# Feedback.net
KiCad netlist of a schematic drawn in Altium Designer
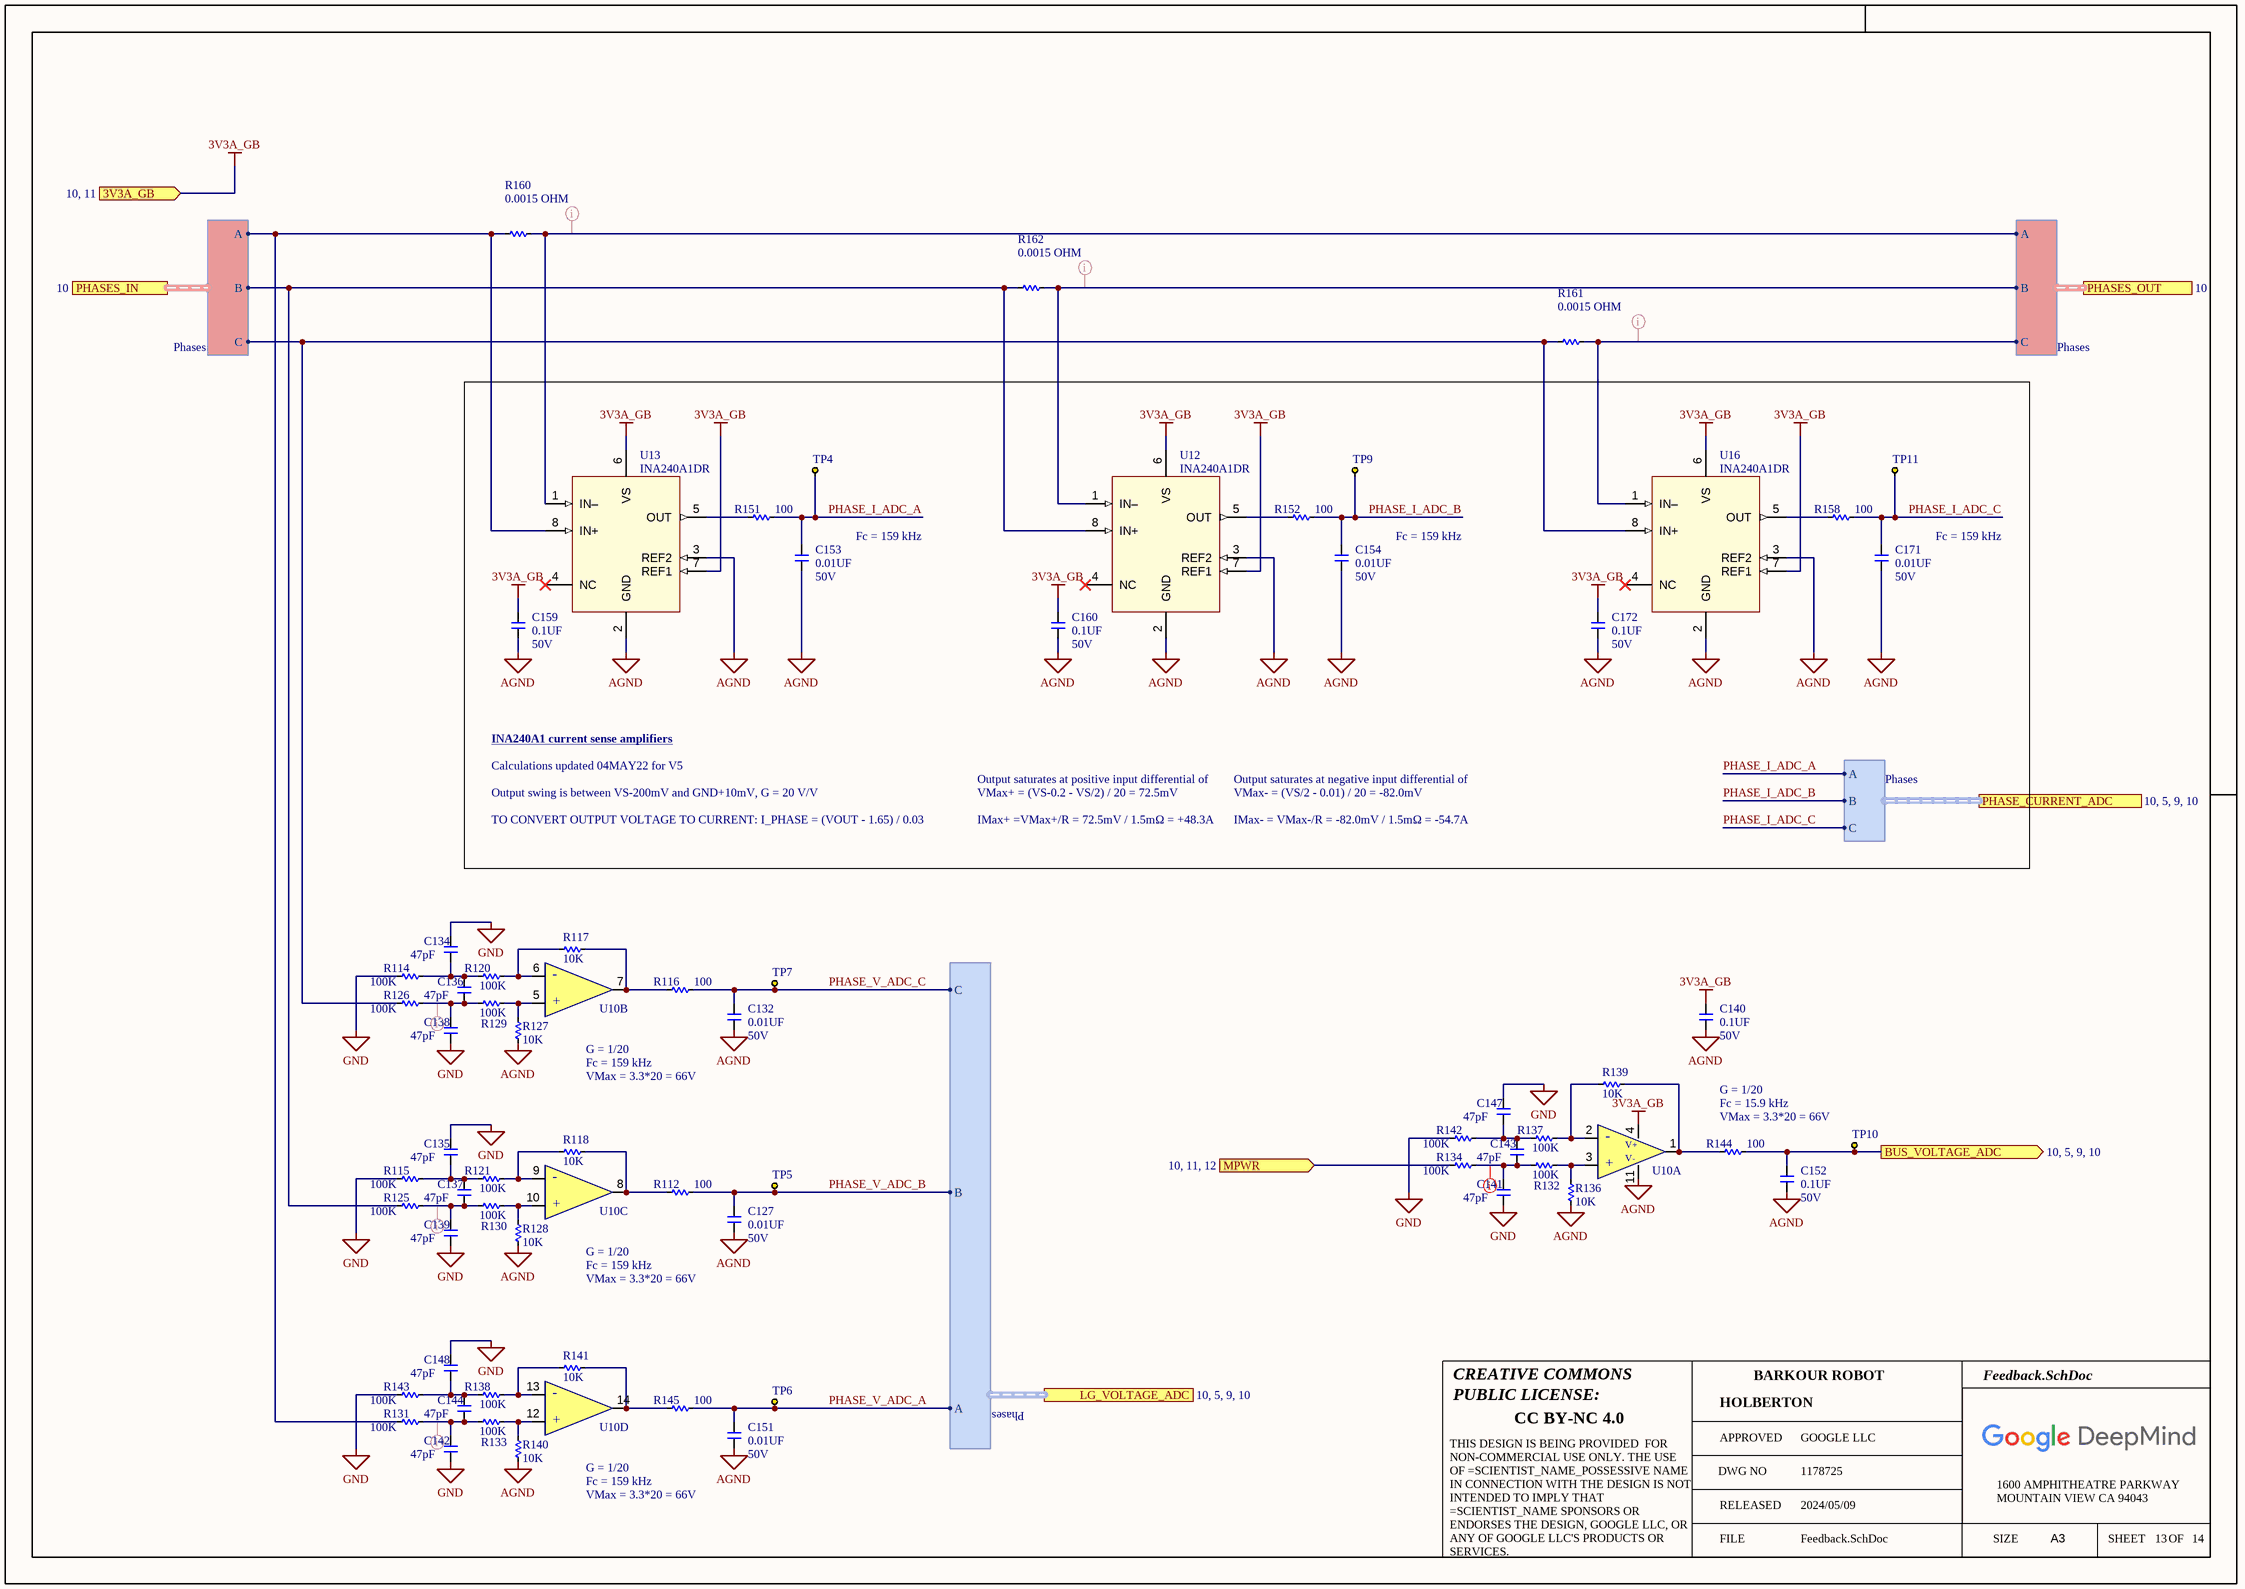
[diagram p0: Feedback.SchDoc]

(export (version "E")
  (design (tool "Eeschema 10.0.6"))
  (components
    (comp (ref "C127")
      (value "0.01UF")
      (footprint "C0402")
      (description "CAP, CER, X7R, 0.01uF, 50V, 20%, 0402, 0.56mm T")
      (fields
        (field (name "MFG") "KEMET")
        (field (name "VOLTAGE") "50V")
        (field (name "Comment") "__Template_Cap")
      )
      (libsource (lib "AltiumReleaseLibDB") (part "__Template_Cap"))
    )
    (comp (ref "C132")
      (value "0.01UF")
      (footprint "C0402")
      (description "CAP, CER, X7R, 0.01uF, 50V, 20%, 0402, 0.56mm T")
      (fields
        (field (name "MFG") "KEMET")
        (field (name "VOLTAGE") "50V")
        (field (name "Comment") "__Template_Cap")
      )
      (libsource (lib "AltiumReleaseLibDB") (part "__Template_Cap"))
    )
    (comp (ref "C134")
      (value "47pF")
      (footprint "C0402")
      (description "CAP, CER, C0G, 47PF, 5%, 50V, 0402")
      (fields (field (name "MFG") "TDK") (field (name "VOLTAGE") "50V"))
      (libsource (lib "AltiumReleaseLibDB") (part "__Template_Cap"))
    )
    (comp (ref "C135")
      (value "47pF")
      (footprint "C0402")
      (description "CAP, CER, C0G, 47PF, 5%, 50V, 0402")
      (fields (field (name "MFG") "TDK") (field (name "VOLTAGE") "50V"))
      (libsource (lib "AltiumReleaseLibDB") (part "__Template_Cap"))
    )
    (comp (ref "C136")
      (value "47pF")
      (footprint "C0402")
      (description "CAP, CER, C0G, 47PF, 5%, 50V, 0402")
      (fields (field (name "MFG") "TDK") (field (name "VOLTAGE") "50V"))
      (libsource (lib "AltiumReleaseLibDB") (part "__Template_Cap"))
    )
    (comp (ref "C137")
      (value "47pF")
      (footprint "C0402")
      (description "CAP, CER, C0G, 47PF, 5%, 50V, 0402")
      (fields (field (name "MFG") "TDK") (field (name "VOLTAGE") "50V"))
      (libsource (lib "AltiumReleaseLibDB") (part "__Template_Cap"))
    )
    (comp (ref "C138")
      (value "47pF")
      (footprint "C0402")
      (description "CAP, CER, C0G, 47PF, 5%, 50V, 0402")
      (fields (field (name "MFG") "TDK") (field (name "VOLTAGE") "50V"))
      (libsource (lib "AltiumReleaseLibDB") (part "__Template_Cap"))
    )
    (comp (ref "C139")
      (value "47pF")
      (footprint "C0402")
      (description "CAP, CER, C0G, 47PF, 5%, 50V, 0402")
      (fields (field (name "MFG") "TDK") (field (name "VOLTAGE") "50V"))
      (libsource (lib "AltiumReleaseLibDB") (part "__Template_Cap"))
    )
    (comp (ref "C140")
      (value "0.1UF")
      (footprint "C0402")
      (description "CAP, CER, X5R, 0.1uF, 10%, 50V, 0402, 0.55mm")
      (fields
        (field (name "MFG") "YAGEO")
        (field (name "VOLTAGE") "50V")
        (field (name "Comment") "__Template_Cap")
      )
      (libsource (lib "AltiumReleaseLibDB") (part "__Template_Cap"))
    )
    (comp (ref "C141")
      (value "47pF")
      (footprint "C0402")
      (description "CAP, CER, C0G, 47PF, 5%, 50V, 0402")
      (fields (field (name "MFG") "TDK") (field (name "VOLTAGE") "50V"))
      (libsource (lib "AltiumReleaseLibDB") (part "__Template_Cap"))
    )
    (comp (ref "C142")
      (value "47pF")
      (footprint "C0402")
      (description "CAP, CER, C0G, 47PF, 5%, 50V, 0402")
      (fields (field (name "MFG") "TDK") (field (name "VOLTAGE") "50V"))
      (libsource (lib "AltiumReleaseLibDB") (part "__Template_Cap"))
    )
    (comp (ref "C143")
      (value "47pF")
      (footprint "C0402")
      (description "CAP, CER, C0G, 47PF, 5%, 50V, 0402")
      (fields (field (name "MFG") "TDK") (field (name "VOLTAGE") "50V"))
      (libsource (lib "AltiumReleaseLibDB") (part "__Template_Cap"))
    )
    (comp (ref "C144")
      (value "47pF")
      (footprint "C0402")
      (description "CAP, CER, C0G, 47PF, 5%, 50V, 0402")
      (fields (field (name "MFG") "TDK") (field (name "VOLTAGE") "50V"))
      (libsource (lib "AltiumReleaseLibDB") (part "__Template_Cap"))
    )
    (comp (ref "C147")
      (value "47pF")
      (footprint "C0402")
      (description "CAP, CER, C0G, 47PF, 5%, 50V, 0402")
      (fields (field (name "MFG") "TDK") (field (name "VOLTAGE") "50V"))
      (libsource (lib "AltiumReleaseLibDB") (part "__Template_Cap"))
    )
    (comp (ref "C148")
      (value "47pF")
      (footprint "C0402")
      (description "CAP, CER, C0G, 47PF, 5%, 50V, 0402")
      (fields (field (name "MFG") "TDK") (field (name "VOLTAGE") "50V"))
      (libsource (lib "AltiumReleaseLibDB") (part "__Template_Cap"))
    )
    (comp (ref "C151")
      (value "0.01UF")
      (footprint "C0402")
      (description "CAP, CER, X7R, 0.01uF, 50V, 20%, 0402, 0.56mm T")
      (fields
        (field (name "MFG") "KEMET")
        (field (name "VOLTAGE") "50V")
        (field (name "Comment") "__Template_Cap")
      )
      (libsource (lib "AltiumReleaseLibDB") (part "__Template_Cap"))
    )
    (comp (ref "C152")
      (value "0.1UF")
      (footprint "C0402")
      (description "CAP, CER, X5R, 0.1uF, 10%, 50V, 0402, 0.55mm")
      (fields
        (field (name "MFG") "YAGEO")
        (field (name "VOLTAGE") "50V")
        (field (name "Comment") "__Template_Cap")
      )
      (libsource (lib "AltiumReleaseLibDB") (part "__Template_Cap"))
    )
    (comp (ref "C153")
      (value "0.01UF")
      (footprint "C0402")
      (description "CAP, CER, X7R, 0.01uF, 50V, 20%, 0402, 0.56mm T")
      (fields
        (field (name "MFG") "KEMET")
        (field (name "VOLTAGE") "50V")
        (field (name "Comment") "__Template_Cap")
      )
      (libsource (lib "AltiumReleaseLibDB") (part "__Template_Cap"))
    )
    (comp (ref "C154")
      (value "0.01UF")
      (footprint "C0402")
      (description "CAP, CER, X7R, 0.01uF, 50V, 20%, 0402, 0.56mm T")
      (fields
        (field (name "MFG") "KEMET")
        (field (name "VOLTAGE") "50V")
        (field (name "Comment") "__Template_Cap")
      )
      (libsource (lib "AltiumReleaseLibDB") (part "__Template_Cap"))
    )
    (comp (ref "C159")
      (value "0.1UF")
      (footprint "C0402")
      (description "CAP, CER, X5R, 0.1uF, 10%, 50V, 0402, 0.55mm")
      (fields
        (field (name "MFG") "YAGEO")
        (field (name "VOLTAGE") "50V")
        (field (name "Comment") "__Template_Cap")
      )
      (libsource (lib "AltiumReleaseLibDB") (part "__Template_Cap"))
    )
    (comp (ref "C160")
      (value "0.1UF")
      (footprint "C0402")
      (description "CAP, CER, X5R, 0.1uF, 10%, 50V, 0402, 0.55mm")
      (fields
        (field (name "MFG") "YAGEO")
        (field (name "VOLTAGE") "50V")
        (field (name "Comment") "__Template_Cap")
      )
      (libsource (lib "AltiumReleaseLibDB") (part "__Template_Cap"))
    )
    (comp (ref "C171")
      (value "0.01UF")
      (footprint "C0402")
      (description "CAP, CER, X7R, 0.01uF, 50V, 20%, 0402, 0.56mm T")
      (fields
        (field (name "MFG") "KEMET")
        (field (name "VOLTAGE") "50V")
        (field (name "Comment") "__Template_Cap")
      )
      (libsource (lib "AltiumReleaseLibDB") (part "__Template_Cap"))
    )
    (comp (ref "C172")
      (value "0.1UF")
      (footprint "C0402")
      (description "CAP, CER, X5R, 0.1uF, 10%, 50V, 0402, 0.55mm")
      (fields
        (field (name "MFG") "YAGEO")
        (field (name "VOLTAGE") "50V")
        (field (name "Comment") "__Template_Cap")
      )
      (libsource (lib "AltiumReleaseLibDB") (part "__Template_Cap"))
    )
    (comp (ref "R112")
      (value "100")
      (footprint "R0402")
      (description "RES, 100, 1%, 1/10W, 0402, AUTO GRADE")
      (fields (field (name "MFG") "PANASONIC"))
      (libsource (lib "AltiumReleaseLibDB") (part "__Template_Resistor"))
    )
    (comp (ref "R114")
      (value "100K")
      (footprint "R0603")
      (description "RES, 100K, 1%, 1/10W, 0603, AUTO GRADE")
      (fields (field (name "MFG") "PANASONIC"))
      (libsource (lib "AltiumReleaseLibDB") (part "__Template_Resistor"))
    )
    (comp (ref "R115")
      (value "100K")
      (footprint "R0603")
      (description "RES, 100K, 1%, 1/10W, 0603, AUTO GRADE")
      (fields (field (name "MFG") "PANASONIC"))
      (libsource (lib "AltiumReleaseLibDB") (part "__Template_Resistor"))
    )
    (comp (ref "R116")
      (value "100")
      (footprint "R0402")
      (description "RES, 100, 1%, 1/10W, 0402, AUTO GRADE")
      (fields (field (name "MFG") "PANASONIC"))
      (libsource (lib "AltiumReleaseLibDB") (part "__Template_Resistor"))
    )
    (comp (ref "R117")
      (value "10K")
      (footprint "R0402")
      (description "RES, 10K, 1%, 1/10W, 0402, AUTOGRADE")
      (fields (field (name "MFG") "PANASONIC"))
      (libsource (lib "AltiumReleaseLibDB") (part "__Template_Resistor"))
    )
    (comp (ref "R118")
      (value "10K")
      (footprint "R0402")
      (description "RES, 10K, 1%, 1/10W, 0402, AUTOGRADE")
      (fields (field (name "MFG") "PANASONIC"))
      (libsource (lib "AltiumReleaseLibDB") (part "__Template_Resistor"))
    )
    (comp (ref "R120")
      (value "100K")
      (footprint "R0603")
      (description "RES, 100K, 1%, 1/10W, 0603, AUTO GRADE")
      (fields (field (name "MFG") "PANASONIC"))
      (libsource (lib "AltiumReleaseLibDB") (part "__Template_Resistor"))
    )
    (comp (ref "R121")
      (value "100K")
      (footprint "R0603")
      (description "RES, 100K, 1%, 1/10W, 0603, AUTO GRADE")
      (fields (field (name "MFG") "PANASONIC"))
      (libsource (lib "AltiumReleaseLibDB") (part "__Template_Resistor"))
    )
    (comp (ref "R125")
      (value "100K")
      (footprint "R0603")
      (description "RES, 100K, 1%, 1/10W, 0603, AUTO GRADE")
      (fields (field (name "MFG") "PANASONIC"))
      (libsource (lib "AltiumReleaseLibDB") (part "__Template_Resistor"))
    )
    (comp (ref "R126")
      (value "100K")
      (footprint "R0603")
      (description "RES, 100K, 1%, 1/10W, 0603, AUTO GRADE")
      (fields (field (name "MFG") "PANASONIC"))
      (libsource (lib "AltiumReleaseLibDB") (part "__Template_Resistor"))
    )
    (comp (ref "R127")
      (value "10K")
      (footprint "R0402")
      (description "RES, 10K, 1%, 1/10W, 0402, AUTOGRADE")
      (fields (field (name "MFG") "PANASONIC"))
      (libsource (lib "AltiumReleaseLibDB") (part "__Template_Resistor"))
    )
    (comp (ref "R128")
      (value "10K")
      (footprint "R0402")
      (description "RES, 10K, 1%, 1/10W, 0402, AUTOGRADE")
      (fields (field (name "MFG") "PANASONIC"))
      (libsource (lib "AltiumReleaseLibDB") (part "__Template_Resistor"))
    )
    (comp (ref "R129")
      (value "100K")
      (footprint "R0603")
      (description "RES, 100K, 1%, 1/10W, 0603, AUTO GRADE")
      (fields (field (name "MFG") "PANASONIC"))
      (libsource (lib "AltiumReleaseLibDB") (part "__Template_Resistor"))
    )
    (comp (ref "R130")
      (value "100K")
      (footprint "R0603")
      (description "RES, 100K, 1%, 1/10W, 0603, AUTO GRADE")
      (fields (field (name "MFG") "PANASONIC"))
      (libsource (lib "AltiumReleaseLibDB") (part "__Template_Resistor"))
    )
    (comp (ref "R131")
      (value "100K")
      (footprint "R0603")
      (description "RES, 100K, 1%, 1/10W, 0603, AUTO GRADE")
      (fields (field (name "MFG") "PANASONIC"))
      (libsource (lib "AltiumReleaseLibDB") (part "__Template_Resistor"))
    )
    (comp (ref "R132")
      (value "100K")
      (footprint "R0603")
      (description "RES, 100K, 1%, 1/10W, 0603, AUTO GRADE")
      (fields (field (name "MFG") "PANASONIC"))
      (libsource (lib "AltiumReleaseLibDB") (part "__Template_Resistor"))
    )
    (comp (ref "R133")
      (value "100K")
      (footprint "R0603")
      (description "RES, 100K, 1%, 1/10W, 0603, AUTO GRADE")
      (fields (field (name "MFG") "PANASONIC"))
      (libsource (lib "AltiumReleaseLibDB") (part "__Template_Resistor"))
    )
    (comp (ref "R134")
      (value "100K")
      (footprint "R0603")
      (description "RES, 100K, 1%, 1/10W, 0603, AUTO GRADE")
      (fields (field (name "MFG") "PANASONIC"))
      (libsource (lib "AltiumReleaseLibDB") (part "__Template_Resistor"))
    )
    (comp (ref "R136")
      (value "10K")
      (footprint "R0402")
      (description "RES, 10K, 1%, 1/10W, 0402, AUTOGRADE")
      (fields (field (name "MFG") "PANASONIC"))
      (libsource (lib "AltiumReleaseLibDB") (part "__Template_Resistor"))
    )
    (comp (ref "R137")
      (value "100K")
      (footprint "R0603")
      (description "RES, 100K, 1%, 1/10W, 0603, AUTO GRADE")
      (fields (field (name "MFG") "PANASONIC"))
      (libsource (lib "AltiumReleaseLibDB") (part "__Template_Resistor"))
    )
    (comp (ref "R138")
      (value "100K")
      (footprint "R0603")
      (description "RES, 100K, 1%, 1/10W, 0603, AUTO GRADE")
      (fields (field (name "MFG") "PANASONIC"))
      (libsource (lib "AltiumReleaseLibDB") (part "__Template_Resistor"))
    )
    (comp (ref "R139")
      (value "10K")
      (footprint "R0402")
      (description "RES, 10K, 1%, 1/10W, 0402, AUTOGRADE")
      (fields (field (name "MFG") "PANASONIC"))
      (libsource (lib "AltiumReleaseLibDB") (part "__Template_Resistor"))
    )
    (comp (ref "R140")
      (value "10K")
      (footprint "R0402")
      (description "RES, 10K, 1%, 1/10W, 0402, AUTOGRADE")
      (fields (field (name "MFG") "PANASONIC"))
      (libsource (lib "AltiumReleaseLibDB") (part "__Template_Resistor"))
    )
    (comp (ref "R141")
      (value "10K")
      (footprint "R0402")
      (description "RES, 10K, 1%, 1/10W, 0402, AUTOGRADE")
      (fields (field (name "MFG") "PANASONIC"))
      (libsource (lib "AltiumReleaseLibDB") (part "__Template_Resistor"))
    )
    (comp (ref "R142")
      (value "100K")
      (footprint "R0603")
      (description "RES, 100K, 1%, 1/10W, 0603, AUTO GRADE")
      (fields (field (name "MFG") "PANASONIC"))
      (libsource (lib "AltiumReleaseLibDB") (part "__Template_Resistor"))
    )
    (comp (ref "R143")
      (value "100K")
      (footprint "R0603")
      (description "RES, 100K, 1%, 1/10W, 0603, AUTO GRADE")
      (fields (field (name "MFG") "PANASONIC"))
      (libsource (lib "AltiumReleaseLibDB") (part "__Template_Resistor"))
    )
    (comp (ref "R144")
      (value "100")
      (footprint "R0402")
      (description "RES, 100, 1%, 1/10W, 0402, AUTO GRADE")
      (fields (field (name "MFG") "PANASONIC"))
      (libsource (lib "AltiumReleaseLibDB") (part "__Template_Resistor"))
    )
    (comp (ref "R145")
      (value "100")
      (footprint "R0402")
      (description "RES, 100, 1%, 1/10W, 0402, AUTO GRADE")
      (fields (field (name "MFG") "PANASONIC"))
      (libsource (lib "AltiumReleaseLibDB") (part "__Template_Resistor"))
    )
    (comp (ref "R151")
      (value "100")
      (footprint "R0402")
      (description "RES, 100, 1%, 1/10W, 0402, AUTO GRADE")
      (fields (field (name "MFG") "PANASONIC"))
      (libsource (lib "AltiumReleaseLibDB") (part "__Template_Resistor"))
    )
    (comp (ref "R152")
      (value "100")
      (footprint "R0402")
      (description "RES, 100, 1%, 1/10W, 0402, AUTO GRADE")
      (fields (field (name "MFG") "PANASONIC"))
      (libsource (lib "AltiumReleaseLibDB") (part "__Template_Resistor"))
    )
    (comp (ref "R158")
      (value "100")
      (footprint "R0402")
      (description "RES, 100, 1%, 1/10W, 0402, AUTO GRADE")
      (fields (field (name "MFG") "PANASONIC"))
      (libsource (lib "AltiumReleaseLibDB") (part "__Template_Resistor"))
    )
    (comp (ref "R160")
      (value "0.0015 OHM")
      (footprint "R2512")
      (description "RES, 0.0015, 1%, 3W, 2512")
      (fields (field (name "MFG") "TE Connectivity Passive Product"))
      (libsource (lib "AltiumReleaseLibDB") (part "__Template_Resistor"))
    )
    (comp (ref "R161")
      (value "0.0015 OHM")
      (footprint "R2512")
      (description "RES, 0.0015, 1%, 3W, 2512")
      (fields (field (name "MFG") "TE Connectivity Passive Product"))
      (libsource (lib "AltiumReleaseLibDB") (part "__Template_Resistor"))
    )
    (comp (ref "R162")
      (value "0.0015 OHM")
      (footprint "R2512")
      (description "RES, 0.0015, 1%, 3W, 2512")
      (fields (field (name "MFG") "TE Connectivity Passive Product"))
      (libsource (lib "AltiumReleaseLibDB") (part "__Template_Resistor"))
    )
    (comp (ref "TP4")
      (value "TEST_KEYSTONE5015")
      (footprint "TP_KEYSTONE_5015")
      (description "PC TEST POINT MINIATURE SMT")
      (fields (field (name "MFG") "Keystone Electronics"))
      (libsource (lib "miscellaneous") (part "TEST_KEYSTONE5015"))
    )
    (comp (ref "TP5")
      (value "TEST_KEYSTONE5015")
      (footprint "TP_KEYSTONE_5015")
      (description "PC TEST POINT MINIATURE SMT")
      (fields (field (name "MFG") "Keystone Electronics"))
      (libsource (lib "miscellaneous") (part "TEST_KEYSTONE5015"))
    )
    (comp (ref "TP6")
      (value "TEST_KEYSTONE5015")
      (footprint "TP_KEYSTONE_5015")
      (description "PC TEST POINT MINIATURE SMT")
      (fields (field (name "MFG") "Keystone Electronics"))
      (libsource (lib "miscellaneous") (part "TEST_KEYSTONE5015"))
    )
    (comp (ref "TP7")
      (value "TEST_KEYSTONE5015")
      (footprint "TP_KEYSTONE_5015")
      (description "PC TEST POINT MINIATURE SMT")
      (fields (field (name "MFG") "Keystone Electronics"))
      (libsource (lib "miscellaneous") (part "TEST_KEYSTONE5015"))
    )
    (comp (ref "TP9")
      (value "TEST_KEYSTONE5015")
      (footprint "TP_KEYSTONE_5015")
      (description "PC TEST POINT MINIATURE SMT")
      (fields (field (name "MFG") "Keystone Electronics"))
      (libsource (lib "miscellaneous") (part "TEST_KEYSTONE5015"))
    )
    (comp (ref "TP10")
      (value "TEST_KEYSTONE5015")
      (footprint "TP_KEYSTONE_5015")
      (description "PC TEST POINT MINIATURE SMT")
      (fields (field (name "MFG") "Keystone Electronics"))
      (libsource (lib "miscellaneous") (part "TEST_KEYSTONE5015"))
    )
    (comp (ref "TP11")
      (value "TEST_KEYSTONE5015")
      (footprint "TP_KEYSTONE_5015")
      (description "PC TEST POINT MINIATURE SMT")
      (fields (field (name "MFG") "Keystone Electronics"))
      (libsource (lib "miscellaneous") (part "TEST_KEYSTONE5015"))
    )
    (comp (ref "U10")
      (value "MCP6064")
      (footprint "14TSSOP65")
      (description "Microchip MCP6064-E/ST; Quad Op Amp; 0.73MHz CMOS; Rail to Rail; 3V; 5V; 14-Pin TSSOP")
      (fields (field (name "MFG") "Microchip Technology"))
      (libsource (lib "MiscSch1") (part "MICROCHIP_MCP6064"))
    )
    (comp (ref "U12")
      (value "INA240A1DR")
      (footprint "TI SOIC-8 D0008A")
      (fields (field (name "MFG") "Texas Instruments"))
      (libsource (lib "MiscSch1") (part "INA240A1"))
    )
    (comp (ref "U13")
      (value "INA240A1DR")
      (footprint "TI SOIC-8 D0008A")
      (fields (field (name "MFG") "Texas Instruments"))
      (libsource (lib "MiscSch1") (part "INA240A1"))
    )
    (comp (ref "U16")
      (value "INA240A1DR")
      (footprint "TI SOIC-8 D0008A")
      (fields (field (name "MFG") "Texas Instruments"))
      (libsource (lib "MiscSch1") (part "INA240A1"))
    )
  )
  (nets
    (net (code "2") (name "/BUS_VOLTAGE_ADC") (class "Default")
      (node (ref "C152") (pin "1") (pintype "passive"))
      (node (ref "R144") (pin "2") (pintype "passive"))
      (node (ref "TP10") (pin "1") (pintype "passive"))
    )
    (net (code "3") (name "/MPWR") (class "Default") (node (ref "R134") (pin "1") (pintype "passive")))
    (net (code "4") (name "/PHASE_I_ADC_A") (class "Default")
      (node (ref "C153") (pin "1") (pintype "passive"))
      (node (ref "R151") (pin "2") (pintype "passive"))
      (node (ref "TP4") (pin "1") (pintype "passive"))
    )
    (net (code "5") (name "/PHASE_I_ADC_B") (class "Default")
      (node (ref "C154") (pin "1") (pintype "passive"))
      (node (ref "R152") (pin "2") (pintype "passive"))
      (node (ref "TP9") (pin "1") (pintype "passive"))
    )
    (net (code "6") (name "/PHASE_I_ADC_C") (class "Default")
      (node (ref "C171") (pin "1") (pintype "passive"))
      (node (ref "R158") (pin "2") (pintype "passive"))
      (node (ref "TP11") (pin "1") (pintype "passive"))
    )
    (net (code "7") (name "/PHASE_V_ADC_A") (class "Default")
      (node (ref "C151") (pin "1") (pintype "passive"))
      (node (ref "R145") (pin "2") (pintype "passive"))
      (node (ref "TP6") (pin "1") (pintype "passive"))
    )
    (net (code "8") (name "/PHASE_V_ADC_B") (class "Default")
      (node (ref "C127") (pin "1") (pintype "passive"))
      (node (ref "R112") (pin "2") (pintype "passive"))
      (node (ref "TP5") (pin "1") (pintype "passive"))
    )
    (net (code "9") (name "/PHASE_V_ADC_C") (class "Default")
      (node (ref "C132") (pin "1") (pintype "passive"))
      (node (ref "R116") (pin "2") (pintype "passive"))
      (node (ref "TP7") (pin "1") (pintype "passive"))
    )
    (net (code "11") (name "3V3A_GB") (class "Default")
      (node (ref "C140") (pin "1") (pintype "passive"))
      (node (ref "C159") (pin "1") (pintype "passive"))
      (node (ref "C160") (pin "1") (pintype "passive"))
      (node (ref "C172") (pin "1") (pintype "passive"))
      (node (ref "U10") (pin "4") (pinfunction "4_4") (pintype "passive"))
      (node (ref "U12") (pin "6") (pinfunction "VS_6") (pintype "power_in"))
      (node (ref "U12") (pin "7") (pinfunction "REF1_7") (pintype "input"))
      (node (ref "U13") (pin "6") (pinfunction "VS_6") (pintype "power_in"))
      (node (ref "U13") (pin "7") (pinfunction "REF1_7") (pintype "input"))
      (node (ref "U16") (pin "6") (pinfunction "VS_6") (pintype "power_in"))
      (node (ref "U16") (pin "7") (pinfunction "REF1_7") (pintype "input"))
    )
    (net (code "12") (name "AGND") (class "Default")
      (node (ref "C127") (pin "2") (pintype "passive"))
      (node (ref "C132") (pin "2") (pintype "passive"))
      (node (ref "C140") (pin "2") (pintype "passive"))
      (node (ref "C151") (pin "2") (pintype "passive"))
      (node (ref "C152") (pin "2") (pintype "passive"))
      (node (ref "C153") (pin "2") (pintype "passive"))
      (node (ref "C154") (pin "2") (pintype "passive"))
      (node (ref "C159") (pin "2") (pintype "passive"))
      (node (ref "C160") (pin "2") (pintype "passive"))
      (node (ref "C171") (pin "2") (pintype "passive"))
      (node (ref "C172") (pin "2") (pintype "passive"))
      (node (ref "R127") (pin "1") (pintype "passive"))
      (node (ref "R128") (pin "1") (pintype "passive"))
      (node (ref "R136") (pin "1") (pintype "passive"))
      (node (ref "R140") (pin "1") (pintype "passive"))
      (node (ref "U10") (pin "11") (pinfunction "11_11") (pintype "passive"))
      (node (ref "U12") (pin "2") (pinfunction "GND_2") (pintype "power_in"))
      (node (ref "U12") (pin "3") (pinfunction "REF2_3") (pintype "input"))
      (node (ref "U13") (pin "2") (pinfunction "GND_2") (pintype "power_in"))
      (node (ref "U13") (pin "3") (pinfunction "REF2_3") (pintype "input"))
      (node (ref "U16") (pin "2") (pinfunction "GND_2") (pintype "power_in"))
      (node (ref "U16") (pin "3") (pinfunction "REF2_3") (pintype "input"))
    )
    (net (code "13") (name "GND") (class "Default")
      (node (ref "C134") (pin "2") (pintype "passive"))
      (node (ref "C135") (pin "2") (pintype "passive"))
      (node (ref "C138") (pin "1") (pintype "passive"))
      (node (ref "C139") (pin "1") (pintype "passive"))
      (node (ref "C141") (pin "1") (pintype "passive"))
      (node (ref "C142") (pin "1") (pintype "passive"))
      (node (ref "C147") (pin "2") (pintype "passive"))
      (node (ref "C148") (pin "2") (pintype "passive"))
      (node (ref "R114") (pin "1") (pintype "passive"))
      (node (ref "R115") (pin "1") (pintype "passive"))
      (node (ref "R142") (pin "1") (pintype "passive"))
      (node (ref "R143") (pin "1") (pintype "passive"))
    )
    (net (code "14") (name "Net-(C134-Pad1)") (class "Default")
      (node (ref "C134") (pin "1") (pintype "passive"))
      (node (ref "C136") (pin "2") (pintype "passive"))
      (node (ref "R114") (pin "2") (pintype "passive"))
      (node (ref "R120") (pin "1") (pintype "passive"))
    )
    (net (code "15") (name "Net-(C135-Pad1)") (class "Default")
      (node (ref "C135") (pin "1") (pintype "passive"))
      (node (ref "C137") (pin "2") (pintype "passive"))
      (node (ref "R115") (pin "2") (pintype "passive"))
      (node (ref "R121") (pin "1") (pintype "passive"))
    )
    (net (code "16") (name "Net-(C136-Pad1)") (class "Default")
      (node (ref "C136") (pin "1") (pintype "passive"))
      (node (ref "C138") (pin "2") (pintype "passive"))
      (node (ref "R126") (pin "2") (pintype "passive"))
      (node (ref "R129") (pin "1") (pintype "passive"))
    )
    (net (code "17") (name "Net-(C137-Pad1)") (class "Default")
      (node (ref "C137") (pin "1") (pintype "passive"))
      (node (ref "C139") (pin "2") (pintype "passive"))
      (node (ref "R125") (pin "2") (pintype "passive"))
      (node (ref "R130") (pin "1") (pintype "passive"))
    )
    (net (code "18") (name "Net-(C141-Pad2)") (class "Default")
      (node (ref "C141") (pin "2") (pintype "passive"))
      (node (ref "C143") (pin "1") (pintype "passive"))
      (node (ref "R132") (pin "1") (pintype "passive"))
      (node (ref "R134") (pin "2") (pintype "passive"))
    )
    (net (code "19") (name "Net-(C142-Pad2)") (class "Default")
      (node (ref "C142") (pin "2") (pintype "passive"))
      (node (ref "C144") (pin "1") (pintype "passive"))
      (node (ref "R131") (pin "2") (pintype "passive"))
      (node (ref "R133") (pin "1") (pintype "passive"))
    )
    (net (code "20") (name "Net-(C143-Pad2)") (class "Default")
      (node (ref "C143") (pin "2") (pintype "passive"))
      (node (ref "C147") (pin "1") (pintype "passive"))
      (node (ref "R137") (pin "1") (pintype "passive"))
      (node (ref "R142") (pin "2") (pintype "passive"))
    )
    (net (code "21") (name "Net-(C144-Pad2)") (class "Default")
      (node (ref "C144") (pin "2") (pintype "passive"))
      (node (ref "C148") (pin "1") (pintype "passive"))
      (node (ref "R138") (pin "1") (pintype "passive"))
      (node (ref "R143") (pin "2") (pintype "passive"))
    )
    (net (code "22") (name "Net-(R112-Pad1)") (class "Default")
      (node (ref "R112") (pin "1") (pintype "passive"))
      (node (ref "R118") (pin "1") (pintype "passive"))
      (node (ref "U10") (pin "8") (pinfunction "8_8") (pintype "passive"))
    )
    (net (code "23") (name "Net-(R116-Pad1)") (class "Default")
      (node (ref "R116") (pin "1") (pintype "passive"))
      (node (ref "R117") (pin "1") (pintype "passive"))
      (node (ref "U10") (pin "7") (pinfunction "7_7") (pintype "passive"))
    )
    (net (code "24") (name "Net-(R117-Pad2)") (class "Default")
      (node (ref "R117") (pin "2") (pintype "passive"))
      (node (ref "R120") (pin "2") (pintype "passive"))
      (node (ref "U10") (pin "6") (pinfunction "6_6") (pintype "passive"))
    )
    (net (code "25") (name "Net-(R118-Pad2)") (class "Default")
      (node (ref "R118") (pin "2") (pintype "passive"))
      (node (ref "R121") (pin "2") (pintype "passive"))
      (node (ref "U10") (pin "9") (pinfunction "9_9") (pintype "passive"))
    )
    (net (code "26") (name "Net-(R127-Pad2)") (class "Default")
      (node (ref "R127") (pin "2") (pintype "passive"))
      (node (ref "R129") (pin "2") (pintype "passive"))
      (node (ref "U10") (pin "5") (pinfunction "5_5") (pintype "passive"))
    )
    (net (code "27") (name "Net-(R128-Pad2)") (class "Default")
      (node (ref "R128") (pin "2") (pintype "passive"))
      (node (ref "R130") (pin "2") (pintype "passive"))
      (node (ref "U10") (pin "10") (pinfunction "10_10") (pintype "passive"))
    )
    (net (code "28") (name "Net-(R132-Pad2)") (class "Default")
      (node (ref "R132") (pin "2") (pintype "passive"))
      (node (ref "R136") (pin "2") (pintype "passive"))
      (node (ref "U10") (pin "3") (pinfunction "3_3") (pintype "passive"))
    )
    (net (code "29") (name "Net-(R133-Pad2)") (class "Default")
      (node (ref "R133") (pin "2") (pintype "passive"))
      (node (ref "R140") (pin "2") (pintype "passive"))
      (node (ref "U10") (pin "12") (pinfunction "12_12") (pintype "passive"))
    )
    (net (code "30") (name "Net-(R137-Pad2)") (class "Default")
      (node (ref "R137") (pin "2") (pintype "passive"))
      (node (ref "R139") (pin "2") (pintype "passive"))
      (node (ref "U10") (pin "2") (pinfunction "2_2") (pintype "passive"))
    )
    (net (code "31") (name "Net-(R138-Pad2)") (class "Default")
      (node (ref "R138") (pin "2") (pintype "passive"))
      (node (ref "R141") (pin "2") (pintype "passive"))
      (node (ref "U10") (pin "13") (pinfunction "13_13") (pintype "passive"))
    )
    (net (code "32") (name "Net-(R139-Pad1)") (class "Default")
      (node (ref "R139") (pin "1") (pintype "passive"))
      (node (ref "R144") (pin "1") (pintype "passive"))
      (node (ref "U10") (pin "1") (pinfunction "1_1") (pintype "passive"))
    )
    (net (code "33") (name "Net-(R141-Pad1)") (class "Default")
      (node (ref "R141") (pin "1") (pintype "passive"))
      (node (ref "R145") (pin "1") (pintype "passive"))
      (node (ref "U10") (pin "14") (pinfunction "14_14") (pintype "passive"))
    )
    (net (code "34") (name "Net-(U12-IN+)") (class "Default")
      (node (ref "R125") (pin "1") (pintype "passive"))
      (node (ref "R162") (pin "1") (pintype "passive"))
      (node (ref "U12") (pin "8") (pinfunction "IN+_8") (pintype "input"))
    )
    (net (code "35") (name "Net-(U12-IN–)") (class "Default")
      (node (ref "R162") (pin "2") (pintype "passive"))
      (node (ref "U12") (pin "1") (pinfunction "IN–_1") (pintype "input"))
    )
    (net (code "36") (name "Net-(U12-OUT)") (class "Default")
      (node (ref "R152") (pin "1") (pintype "passive"))
      (node (ref "U12") (pin "5") (pinfunction "OUT_5") (pintype "output"))
    )
    (net (code "37") (name "Net-(U13-IN+)") (class "Default")
      (node (ref "R131") (pin "1") (pintype "passive"))
      (node (ref "R160") (pin "1") (pintype "passive"))
      (node (ref "U13") (pin "8") (pinfunction "IN+_8") (pintype "input"))
    )
    (net (code "38") (name "Net-(U13-IN–)") (class "Default")
      (node (ref "R160") (pin "2") (pintype "passive"))
      (node (ref "U13") (pin "1") (pinfunction "IN–_1") (pintype "input"))
    )
    (net (code "39") (name "Net-(U13-OUT)") (class "Default")
      (node (ref "R151") (pin "1") (pintype "passive"))
      (node (ref "U13") (pin "5") (pinfunction "OUT_5") (pintype "output"))
    )
    (net (code "40") (name "Net-(U16-IN+)") (class "Default")
      (node (ref "R126") (pin "1") (pintype "passive"))
      (node (ref "R161") (pin "1") (pintype "passive"))
      (node (ref "U16") (pin "8") (pinfunction "IN+_8") (pintype "input"))
    )
    (net (code "41") (name "Net-(U16-IN–)") (class "Default")
      (node (ref "R161") (pin "2") (pintype "passive"))
      (node (ref "U16") (pin "1") (pinfunction "IN–_1") (pintype "input"))
    )
    (net (code "42") (name "Net-(U16-OUT)") (class "Default")
      (node (ref "R158") (pin "1") (pintype "passive"))
      (node (ref "U16") (pin "5") (pinfunction "OUT_5") (pintype "output"))
    )
    (net (code "43") (name "unconnected-(U12-NC-Pad4)") (class "Default")
      (node (ref "U12") (pin "4") (pinfunction "NC_4") (pintype "passive+no_connect"))
    )
    (net (code "44") (name "unconnected-(U13-NC-Pad4)") (class "Default")
      (node (ref "U13") (pin "4") (pinfunction "NC_4") (pintype "passive+no_connect"))
    )
    (net (code "45") (name "unconnected-(U16-NC-Pad4)") (class "Default")
      (node (ref "U16") (pin "4") (pinfunction "NC_4") (pintype "passive+no_connect"))
    )
  )
)
